# SCH_PowerDistributionBoardV2_2022-03-02.net
KiCad netlist of a schematic drawn in EasyEDA
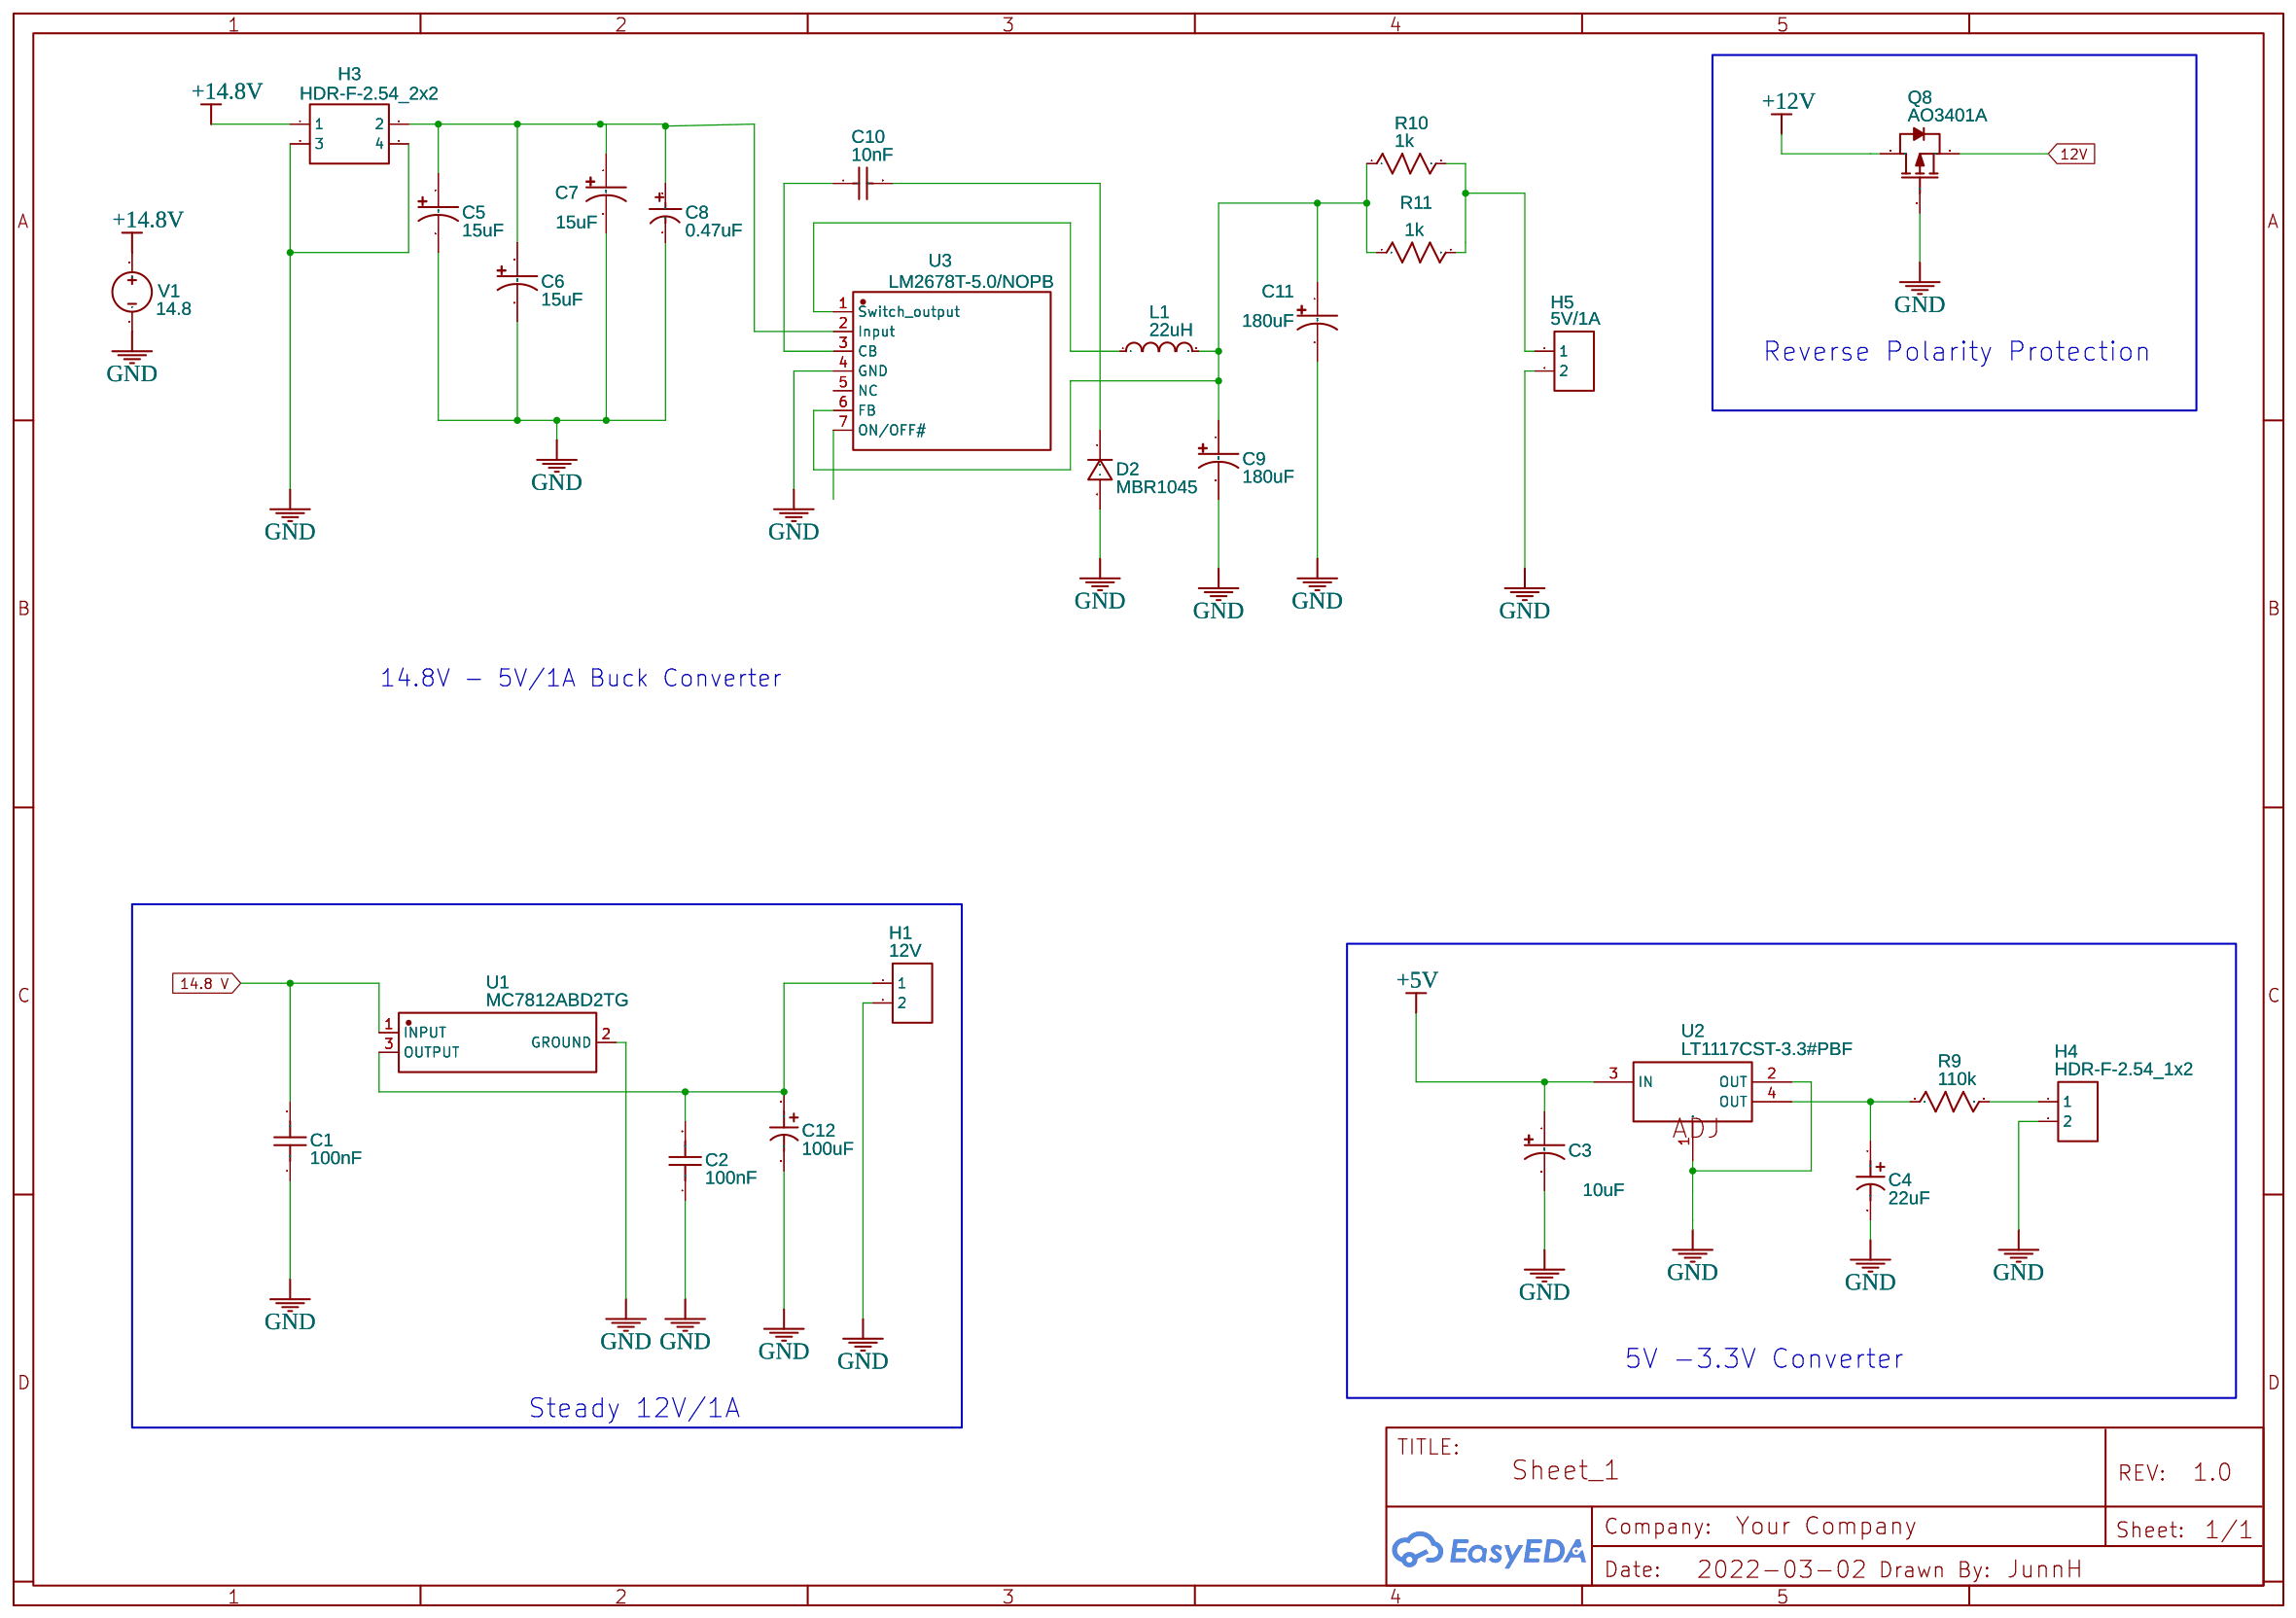
[diagram p0: schematic sheet]

(export (version "E")
  (design (tool "Eeschema 10.0.6"))
  (components
    (comp (ref "C1")
      (value "100nF")
      (fields
        (field (name "BOM_Manufacturer Part") "CC1H104ZA19D3F5P10MF")
        (field (name "BOM_Supplier Part") "C254086")
      )
      (libsource (lib "") (part "CC1H104ZA19D3F5P10MF"))
    )
    (comp (ref "C2")
      (value "100nF")
      (fields
        (field (name "BOM_Manufacturer Part") "CC1H104ZA19D3F5P10MF")
        (field (name "BOM_Supplier Part") "C254086")
      )
      (libsource (lib "") (part "CC1H104ZA19D3F5P10MF"))
    )
    (comp (ref "C3")
      (value "10uF")
      (fields
        (field (name "BOM_Manufacturer Part") "VE-100M1H0505-TRO")
        (field (name "BOM_Supplier Part") "C249452")
      )
      (libsource (lib "") (part "VE-100M1H0505-TRO"))
    )
    (comp (ref "C4")
      (value "22uF")
      (fields
        (field (name "BOM_Manufacturer Part") "RVT22UF50V67RV0028")
        (field (name "BOM_Supplier Part") "C2836438")
      )
      (libsource (lib "") (part "RVT22UF50V67RV0028"))
    )
    (comp (ref "C5")
      (value "15uF")
      (fields
        (field (name "BOM_Manufacturer Part") "UUD1H150MCL1GS")
        (field (name "BOM_Supplier Part") "C340748")
      )
      (libsource (lib "") (part "UUD1H150MCL1GS"))
    )
    (comp (ref "C6")
      (value "15uF")
      (fields
        (field (name "BOM_Manufacturer Part") "UUD1H150MCL1GS")
        (field (name "BOM_Supplier Part") "C340748")
      )
      (libsource (lib "") (part "UUD1H150MCL1GS"))
    )
    (comp (ref "C7")
      (value "15uF")
      (fields
        (field (name "BOM_Manufacturer Part") "UUD1H150MCL1GS")
        (field (name "BOM_Supplier Part") "C340748")
      )
      (libsource (lib "") (part "UUD1H150MCL1GS_1"))
    )
    (comp (ref "C8")
      (value "0.47uF")
      (fields
        (field (name "BOM_Manufacturer Part") "CS1HR47M-CRC54")
        (field (name "BOM_Supplier Part") "C117834")
      )
      (libsource (lib "") (part "CS1HR47M-CRC54"))
    )
    (comp (ref "C9")
      (value "180uF")
      (fields
        (field (name "BOM_Manufacturer Part") "VKMC1001C181MV")
        (field (name "BOM_Supplier Part") "C487303")
      )
      (libsource (lib "") (part "VKMC1001C181MV"))
    )
    (comp (ref "C10")
      (value "10nF")
      (fields
        (field (name "BOM_Manufacturer Part") "CL21B103KBANNNC")
        (field (name "BOM_Supplier Part") "C1710")
      )
      (libsource (lib "") (part "CL21B103KBANNNC"))
    )
    (comp (ref "C11")
      (value "180uF")
      (fields
        (field (name "BOM_Manufacturer Part") "VKMC1001C181MV")
        (field (name "BOM_Supplier Part") "C487303")
      )
      (libsource (lib "") (part "VKMC1001C181MV"))
    )
    (comp (ref "C12")
      (value "100uF")
      (fields
        (field (name "BOM_Manufacturer Part") "RVT100UF35V67RV0034")
        (field (name "BOM_Supplier Part") "C2836442")
      )
      (libsource (lib "") (part "RVT100UF35V67RV0034"))
    )
    (comp (ref "D2")
      (value "MBR1045")
      (fields (field (name "BOM_Supplier Part") "C260253"))
      (libsource (lib "") (part "MBR1045"))
    )
    (comp (ref "H1")
      (value "12V")
      (fields (field (name "BOM_Supplier Part") "C49661"))
      (libsource (lib "") (part "HDR-F-2.54_1x2"))
    )
    (comp (ref "H3")
      (value "HDR-F-2.54_2x2")
      (fields (field (name "BOM_Supplier Part") "C239342"))
      (libsource (lib "") (part "HDR-F-2.54_2x2"))
    )
    (comp (ref "H4")
      (value "HDR-F-2.54_1x2")
      (fields (field (name "BOM_Supplier Part") "C49661"))
      (libsource (lib "") (part "HDR-F-2.54_1x2"))
    )
    (comp (ref "H5")
      (value "5V/1A")
      (fields (field (name "BOM_Supplier Part") "C49661"))
      (libsource (lib "") (part "HDR-F-2.54_1x2"))
    )
    (comp (ref "L1")
      (value "22uH")
      (fields
        (field (name "BOM_Manufacturer Part") "SLO0630H220MTT")
        (field (name "BOM_Supplier Part") "C207843")
      )
      (libsource (lib "") (part "SLO0630H220MTT"))
    )
    (comp (ref "Q8")
      (value "AO3401A")
      (fields (field (name "BOM_Supplier Part") "C15127"))
      (libsource (lib "") (part "AO3401A"))
    )
    (comp (ref "R9") (value "110k") (libsource (lib "") (part "R_0603_US")))
    (comp (ref "R10") (value "1k") (libsource (lib "") (part "R_0603_US")))
    (comp (ref "R11") (value "1k") (libsource (lib "") (part "R_0603_US")))
    (comp (ref "U1")
      (value "MC7812ABD2TG")
      (fields (field (name "BOM_Supplier Part") "C154818"))
      (libsource (lib "") (part "MC7812ABD2TG"))
    )
    (comp (ref "U2")
      (value "LT1117CST-3.3#PBF")
      (fields (field (name "BOM_Supplier Part") "C140395"))
      (libsource (lib "") (part "LT1117CST-3.3#PBF"))
    )
    (comp (ref "U3")
      (value "LM2678T-5.0/NOPB")
      (fields (field (name "BOM_Supplier Part") "C390086"))
      (libsource (lib "") (part "LM2678T-5.0/NOPB"))
    )
    (comp (ref "V1") (value "14.8") (libsource (lib "") (part "VDC")))
  )
  (nets
    (net (code "1") (name "+5V") (class "Default")
      (node (ref "C3") (pin "1") (pinfunction "1_1") (pintype "unspecified"))
      (node (ref "U2") (pin "3") (pinfunction "IN_3") (pintype "passive"))
    )
    (net (code "2") (name "+12V") (class "Default")
      (node (ref "Q8") (pin "3") (pinfunction "D_3") (pintype "unspecified"))
    )
    (net (code "3") (name "+14.8V") (class "Default")
      (node (ref "H3") (pin "1") (pinfunction "1_1") (pintype "unspecified"))
      (node (ref "V1") (pin "1") (pinfunction "1_1") (pintype "unspecified"))
    )
    (net (code "4") (name "12V") (class "Default")
      (node (ref "Q8") (pin "2") (pinfunction "S_2") (pintype "unspecified"))
    )
    (net (code "5") (name "14.8 V") (class "Default")
      (node (ref "C1") (pin "2") (pinfunction "2_2") (pintype "unspecified"))
      (node (ref "U1") (pin "1") (pinfunction "INPUT_1") (pintype "unspecified"))
    )
    (net (code "6") (name "GND") (class "Default")
      (node (ref "C1") (pin "1") (pinfunction "1_1") (pintype "unspecified"))
      (node (ref "C11") (pin "2") (pinfunction "2_2") (pintype "unspecified"))
      (node (ref "C12") (pin "2") (pinfunction "2_2") (pintype "input"))
      (node (ref "C2") (pin "1") (pinfunction "1_1") (pintype "unspecified"))
      (node (ref "C3") (pin "2") (pinfunction "2_2") (pintype "unspecified"))
      (node (ref "C4") (pin "2") (pinfunction "2_2") (pintype "input"))
      (node (ref "C5") (pin "2") (pinfunction "2_2") (pintype "unspecified"))
      (node (ref "C6") (pin "2") (pinfunction "2_2") (pintype "unspecified"))
      (node (ref "C7") (pin "2") (pinfunction "2_2") (pintype "unspecified"))
      (node (ref "C8") (pin "2") (pinfunction "2_2") (pintype "input"))
      (node (ref "C9") (pin "2") (pinfunction "2_2") (pintype "unspecified"))
      (node (ref "D2") (pin "2") (pinfunction "A_2") (pintype "unspecified"))
      (node (ref "H1") (pin "2") (pinfunction "2_2") (pintype "input"))
      (node (ref "H3") (pin "3") (pinfunction "3_3") (pintype "unspecified"))
      (node (ref "H3") (pin "4") (pinfunction "4_4") (pintype "unspecified"))
      (node (ref "H4") (pin "2") (pinfunction "2_2") (pintype "input"))
      (node (ref "H5") (pin "2") (pinfunction "2_2") (pintype "input"))
      (node (ref "Q8") (pin "1") (pinfunction "G_1") (pintype "unspecified"))
      (node (ref "U1") (pin "2") (pinfunction "GROUND_2") (pintype "unspecified"))
      (node (ref "U2") (pin "1") (pinfunction "ADJ_1") (pintype "passive"))
      (node (ref "U2") (pin "2") (pinfunction "OUT_2") (pintype "passive"))
      (node (ref "U3") (pin "4") (pinfunction "GND_4") (pintype "unspecified"))
      (node (ref "V1") (pin "2") (pinfunction "2_2") (pintype "unspecified"))
    )
    (net (code "7") (name "Net-(C4-Pad1)") (class "Default")
      (node (ref "C4") (pin "1") (pinfunction "1_1") (pintype "input"))
      (node (ref "R9") (pin "1") (pinfunction "1_1") (pintype "unspecified"))
      (node (ref "U2") (pin "4") (pinfunction "OUT_4") (pintype "passive"))
    )
    (net (code "8") (name "Net-(D2-C)") (class "Default")
      (node (ref "C10") (pin "2") (pinfunction "2_2") (pintype "input"))
      (node (ref "D2") (pin "1") (pinfunction "C_1") (pintype "unspecified"))
    )
    (net (code "9") (name "Net-(H4-Pad1)") (class "Default")
      (node (ref "H4") (pin "1") (pinfunction "1_1") (pintype "input"))
      (node (ref "R9") (pin "2") (pinfunction "2_2") (pintype "unspecified"))
    )
    (net (code "10") (name "Net-(H5-Pad1)") (class "Default")
      (node (ref "H5") (pin "1") (pinfunction "1_1") (pintype "input"))
      (node (ref "R10") (pin "2") (pinfunction "2_2") (pintype "unspecified"))
      (node (ref "R11") (pin "2") (pinfunction "2_2") (pintype "unspecified"))
    )
    (net (code "11") (name "Net-(U1-OUTPUT)") (class "Default")
      (node (ref "C12") (pin "1") (pinfunction "1_1") (pintype "input"))
      (node (ref "C2") (pin "2") (pinfunction "2_2") (pintype "unspecified"))
      (node (ref "H1") (pin "1") (pinfunction "1_1") (pintype "input"))
      (node (ref "U1") (pin "3") (pinfunction "OUTPUT_3") (pintype "unspecified"))
    )
    (net (code "12") (name "Net-(U3-CB)") (class "Default")
      (node (ref "C10") (pin "1") (pinfunction "1_1") (pintype "input"))
      (node (ref "U3") (pin "3") (pinfunction "CB_3") (pintype "unspecified"))
    )
    (net (code "13") (name "Net-(U3-FB)") (class "Default")
      (node (ref "C11") (pin "1") (pinfunction "1_1") (pintype "unspecified"))
      (node (ref "C9") (pin "1") (pinfunction "1_1") (pintype "unspecified"))
      (node (ref "L1") (pin "2") (pinfunction "2_2") (pintype "unspecified"))
      (node (ref "R10") (pin "1") (pinfunction "1_1") (pintype "unspecified"))
      (node (ref "R11") (pin "1") (pinfunction "1_1") (pintype "unspecified"))
      (node (ref "U3") (pin "6") (pinfunction "FB_6") (pintype "unspecified"))
    )
    (net (code "14") (name "Net-(U3-Input)") (class "Default")
      (node (ref "C5") (pin "1") (pinfunction "1_1") (pintype "unspecified"))
      (node (ref "C6") (pin "1") (pinfunction "1_1") (pintype "unspecified"))
      (node (ref "C7") (pin "1") (pinfunction "1_1") (pintype "unspecified"))
      (node (ref "C8") (pin "1") (pinfunction "1_1") (pintype "input"))
      (node (ref "H3") (pin "2") (pinfunction "2_2") (pintype "unspecified"))
      (node (ref "U3") (pin "2") (pinfunction "Input_2") (pintype "unspecified"))
    )
    (net (code "15") (name "Net-(U3-Switch_output)") (class "Default")
      (node (ref "L1") (pin "1") (pinfunction "1_1") (pintype "unspecified"))
      (node (ref "U3") (pin "1") (pinfunction "Switch_output_1") (pintype "unspecified"))
    )
    (net (code "16") (name "unconnected-(U3-NC-Pad5)") (class "Default")
      (node (ref "U3") (pin "5") (pinfunction "NC_5") (pintype "unspecified"))
    )
    (net (code "17") (name "unconnected-(U3-ON{slash}OFF#-Pad7)") (class "Default")
      (node (ref "U3") (pin "7") (pinfunction "ON/OFF#_7") (pintype "unspecified"))
    )
  )
)
